# RP_ComputeModule3_rev_3_0_GPIOs.net
KiCad netlist of a schematic drawn in Altium Designer
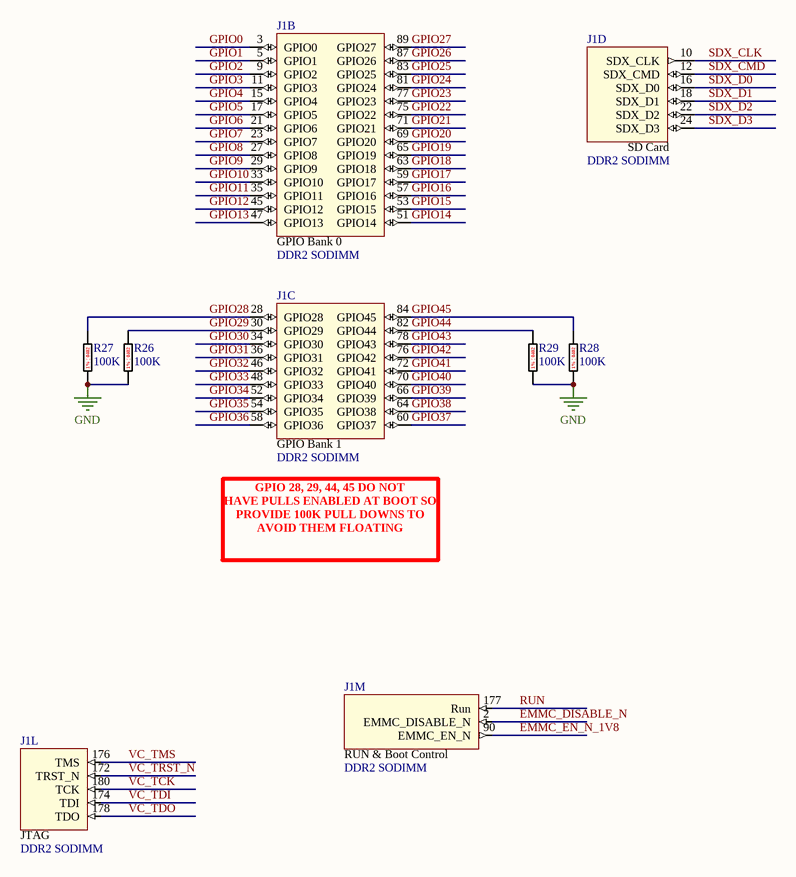
[diagram p0: RP_ComputeModule3_rev.3.0_GPIOs.SchDoc]

(export (version "E")
  (design (tool "Eeschema 10.0.6"))
  (components
    (comp (ref "J1")
      (value "DDR2 SODIMM")
      (footprint "TE 1473005-4 (DDR2 SO-DIMM)")
      (description "TE CONNECTIVITY / AMP         1473005-4             SOCKET IC, DIMM, DDR2, 1.8V, 200WAY")
      (fields
        (field (name "MANUFACTURER") "TE Connectivity")
        (field (name "MANUFACTURER PART NUMBER") "1473005-4")
      )
      (libsource (lib "TEConnectivity_AMP") (part "1473005-4"))
    )
    (comp (ref "R26")
      (value "100K")
      (footprint "RES0402")
      (description "Thick Film Resistors - SMD 0.125W 100Kohm 1% 200ppm")
      (fields
        (field (name "MANUFACTURER") "KOA Speer")
        (field (name "MANUFACTURER PART NUMBER") "SG73P1ETTP1003F")
      )
      (libsource (lib "KOA_Resistors") (part "SG73P1ETTP1003F"))
    )
    (comp (ref "R27")
      (value "100K")
      (footprint "RES0402")
      (description "Thick Film Resistors - SMD 0.125W 100Kohm 1% 200ppm")
      (fields
        (field (name "MANUFACTURER") "KOA Speer")
        (field (name "MANUFACTURER PART NUMBER") "SG73P1ETTP1003F")
      )
      (libsource (lib "KOA_Resistors") (part "SG73P1ETTP1003F"))
    )
    (comp (ref "R28")
      (value "100K")
      (footprint "RES0402")
      (description "Thick Film Resistors - SMD 0.125W 100Kohm 1% 200ppm")
      (fields
        (field (name "MANUFACTURER") "KOA Speer")
        (field (name "MANUFACTURER PART NUMBER") "SG73P1ETTP1003F")
      )
      (libsource (lib "KOA_Resistors") (part "SG73P1ETTP1003F"))
    )
    (comp (ref "R29")
      (value "100K")
      (footprint "RES0402")
      (description "Thick Film Resistors - SMD 0.125W 100Kohm 1% 200ppm")
      (fields
        (field (name "MANUFACTURER") "KOA Speer")
        (field (name "MANUFACTURER PART NUMBER") "SG73P1ETTP1003F")
      )
      (libsource (lib "KOA_Resistors") (part "SG73P1ETTP1003F"))
    )
  )
  (nets
    (net (code "1") (name "/EMMC_DISABLE_N") (class "Default")
      (node (ref "J1") (pin "2") (pinfunction "EMMC_DISABLE_N_2") (pintype "input"))
    )
    (net (code "2") (name "/EMMC_EN_N_1V8") (class "Default")
      (node (ref "J1") (pin "90") (pinfunction "EMMC_EN_N_90") (pintype "output"))
    )
    (net (code "3") (name "/GPIO0") (class "Default")
      (node (ref "J1") (pin "3") (pinfunction "GPIO0_3") (pintype "bidirectional"))
    )
    (net (code "4") (name "/GPIO1") (class "Default")
      (node (ref "J1") (pin "5") (pinfunction "GPIO1_5") (pintype "bidirectional"))
    )
    (net (code "5") (name "/GPIO2") (class "Default")
      (node (ref "J1") (pin "9") (pinfunction "GPIO2_9") (pintype "bidirectional"))
    )
    (net (code "6") (name "/GPIO3") (class "Default")
      (node (ref "J1") (pin "11") (pinfunction "GPIO3_11") (pintype "bidirectional"))
    )
    (net (code "7") (name "/GPIO4") (class "Default")
      (node (ref "J1") (pin "15") (pinfunction "GPIO4_15") (pintype "bidirectional"))
    )
    (net (code "8") (name "/GPIO5") (class "Default")
      (node (ref "J1") (pin "17") (pinfunction "GPIO5_17") (pintype "bidirectional"))
    )
    (net (code "9") (name "/GPIO6") (class "Default")
      (node (ref "J1") (pin "21") (pinfunction "GPIO6_21") (pintype "bidirectional"))
    )
    (net (code "10") (name "/GPIO7") (class "Default")
      (node (ref "J1") (pin "23") (pinfunction "GPIO7_23") (pintype "bidirectional"))
    )
    (net (code "11") (name "/GPIO8") (class "Default")
      (node (ref "J1") (pin "27") (pinfunction "GPIO8_27") (pintype "bidirectional"))
    )
    (net (code "12") (name "/GPIO9") (class "Default")
      (node (ref "J1") (pin "29") (pinfunction "GPIO9_29") (pintype "bidirectional"))
    )
    (net (code "13") (name "/GPIO10") (class "Default")
      (node (ref "J1") (pin "33") (pinfunction "GPIO10_33") (pintype "bidirectional"))
    )
    (net (code "14") (name "/GPIO11") (class "Default")
      (node (ref "J1") (pin "35") (pinfunction "GPIO11_35") (pintype "bidirectional"))
    )
    (net (code "15") (name "/GPIO12") (class "Default")
      (node (ref "J1") (pin "45") (pinfunction "GPIO12_45") (pintype "bidirectional"))
    )
    (net (code "16") (name "/GPIO13") (class "Default")
      (node (ref "J1") (pin "47") (pinfunction "GPIO13_47") (pintype "bidirectional"))
    )
    (net (code "17") (name "/GPIO14") (class "Default")
      (node (ref "J1") (pin "51") (pinfunction "GPIO14_51") (pintype "bidirectional"))
    )
    (net (code "18") (name "/GPIO15") (class "Default")
      (node (ref "J1") (pin "53") (pinfunction "GPIO15_53") (pintype "bidirectional"))
    )
    (net (code "19") (name "/GPIO16") (class "Default")
      (node (ref "J1") (pin "57") (pinfunction "GPIO16_57") (pintype "bidirectional"))
    )
    (net (code "20") (name "/GPIO17") (class "Default")
      (node (ref "J1") (pin "59") (pinfunction "GPIO17_59") (pintype "bidirectional"))
    )
    (net (code "21") (name "/GPIO18") (class "Default")
      (node (ref "J1") (pin "63") (pinfunction "GPIO18_63") (pintype "bidirectional"))
    )
    (net (code "22") (name "/GPIO19") (class "Default")
      (node (ref "J1") (pin "65") (pinfunction "GPIO19_65") (pintype "bidirectional"))
    )
    (net (code "23") (name "/GPIO20") (class "Default")
      (node (ref "J1") (pin "69") (pinfunction "GPIO20_69") (pintype "bidirectional"))
    )
    (net (code "24") (name "/GPIO21") (class "Default")
      (node (ref "J1") (pin "71") (pinfunction "GPIO21_71") (pintype "bidirectional"))
    )
    (net (code "25") (name "/GPIO22") (class "Default")
      (node (ref "J1") (pin "75") (pinfunction "GPIO22_75") (pintype "bidirectional"))
    )
    (net (code "26") (name "/GPIO23") (class "Default")
      (node (ref "J1") (pin "77") (pinfunction "GPIO23_77") (pintype "bidirectional"))
    )
    (net (code "27") (name "/GPIO24") (class "Default")
      (node (ref "J1") (pin "81") (pinfunction "GPIO24_81") (pintype "bidirectional"))
    )
    (net (code "28") (name "/GPIO25") (class "Default")
      (node (ref "J1") (pin "83") (pinfunction "GPIO25_83") (pintype "bidirectional"))
    )
    (net (code "29") (name "/GPIO26") (class "Default")
      (node (ref "J1") (pin "87") (pinfunction "GPIO26_87") (pintype "bidirectional"))
    )
    (net (code "30") (name "/GPIO27") (class "Default")
      (node (ref "J1") (pin "89") (pinfunction "GPIO27_89") (pintype "bidirectional"))
    )
    (net (code "31") (name "/GPIO28") (class "Default")
      (node (ref "J1") (pin "28") (pinfunction "GPIO28_28") (pintype "bidirectional"))
      (node (ref "R27") (pin "1") (pinfunction "1_1") (pintype "passive"))
    )
    (net (code "32") (name "/GPIO29") (class "Default")
      (node (ref "J1") (pin "30") (pinfunction "GPIO29_30") (pintype "bidirectional"))
      (node (ref "R26") (pin "1") (pinfunction "1_1") (pintype "passive"))
    )
    (net (code "33") (name "/GPIO30") (class "Default")
      (node (ref "J1") (pin "34") (pinfunction "GPIO30_34") (pintype "bidirectional"))
    )
    (net (code "34") (name "/GPIO31") (class "Default")
      (node (ref "J1") (pin "36") (pinfunction "GPIO31_36") (pintype "bidirectional"))
    )
    (net (code "35") (name "/GPIO32") (class "Default")
      (node (ref "J1") (pin "46") (pinfunction "GPIO32_46") (pintype "bidirectional"))
    )
    (net (code "36") (name "/GPIO33") (class "Default")
      (node (ref "J1") (pin "48") (pinfunction "GPIO33_48") (pintype "bidirectional"))
    )
    (net (code "37") (name "/GPIO34") (class "Default")
      (node (ref "J1") (pin "52") (pinfunction "GPIO34_52") (pintype "bidirectional"))
    )
    (net (code "38") (name "/GPIO35") (class "Default")
      (node (ref "J1") (pin "54") (pinfunction "GPIO35_54") (pintype "bidirectional"))
    )
    (net (code "39") (name "/GPIO36") (class "Default")
      (node (ref "J1") (pin "58") (pinfunction "GPIO36_58") (pintype "bidirectional"))
    )
    (net (code "40") (name "/GPIO37") (class "Default")
      (node (ref "J1") (pin "60") (pinfunction "GPIO37_60") (pintype "bidirectional"))
    )
    (net (code "41") (name "/GPIO38") (class "Default")
      (node (ref "J1") (pin "64") (pinfunction "GPIO38_64") (pintype "bidirectional"))
    )
    (net (code "42") (name "/GPIO39") (class "Default")
      (node (ref "J1") (pin "66") (pinfunction "GPIO39_66") (pintype "bidirectional"))
    )
    (net (code "43") (name "/GPIO40") (class "Default")
      (node (ref "J1") (pin "70") (pinfunction "GPIO40_70") (pintype "bidirectional"))
    )
    (net (code "44") (name "/GPIO41") (class "Default")
      (node (ref "J1") (pin "72") (pinfunction "GPIO41_72") (pintype "bidirectional"))
    )
    (net (code "45") (name "/GPIO42") (class "Default")
      (node (ref "J1") (pin "76") (pinfunction "GPIO42_76") (pintype "bidirectional"))
    )
    (net (code "46") (name "/GPIO43") (class "Default")
      (node (ref "J1") (pin "78") (pinfunction "GPIO43_78") (pintype "bidirectional"))
    )
    (net (code "47") (name "/GPIO44") (class "Default")
      (node (ref "J1") (pin "82") (pinfunction "GPIO44_82") (pintype "bidirectional"))
      (node (ref "R29") (pin "1") (pinfunction "1_1") (pintype "passive"))
    )
    (net (code "48") (name "/GPIO45") (class "Default")
      (node (ref "J1") (pin "84") (pinfunction "GPIO45_84") (pintype "bidirectional"))
      (node (ref "R28") (pin "1") (pinfunction "1_1") (pintype "passive"))
    )
    (net (code "49") (name "/RUN") (class "Default")
      (node (ref "J1") (pin "177") (pinfunction "Run_177") (pintype "input"))
    )
    (net (code "50") (name "/SDX_CLK") (class "Default")
      (node (ref "J1") (pin "10") (pinfunction "SDX_CLK_10") (pintype "output"))
    )
    (net (code "51") (name "/SDX_CMD") (class "Default")
      (node (ref "J1") (pin "12") (pinfunction "SDX_CMD_12") (pintype "bidirectional"))
    )
    (net (code "52") (name "/SDX_D0") (class "Default")
      (node (ref "J1") (pin "16") (pinfunction "SDX_D0_16") (pintype "bidirectional"))
    )
    (net (code "53") (name "/SDX_D1") (class "Default")
      (node (ref "J1") (pin "18") (pinfunction "SDX_D1_18") (pintype "bidirectional"))
    )
    (net (code "54") (name "/SDX_D2") (class "Default")
      (node (ref "J1") (pin "22") (pinfunction "SDX_D2_22") (pintype "bidirectional"))
    )
    (net (code "55") (name "/SDX_D3") (class "Default")
      (node (ref "J1") (pin "24") (pinfunction "SDX_D3_24") (pintype "bidirectional"))
    )
    (net (code "56") (name "/VC_TCK") (class "Default")
      (node (ref "J1") (pin "180") (pinfunction "TCK_180") (pintype "input"))
    )
    (net (code "57") (name "/VC_TDI") (class "Default")
      (node (ref "J1") (pin "174") (pinfunction "TDI_174") (pintype "input"))
    )
    (net (code "58") (name "/VC_TDO") (class "Default")
      (node (ref "J1") (pin "178") (pinfunction "TDO_178") (pintype "input"))
    )
    (net (code "59") (name "/VC_TMS") (class "Default")
      (node (ref "J1") (pin "176") (pinfunction "TMS_176") (pintype "input"))
    )
    (net (code "60") (name "/VC_TRST_N") (class "Default")
      (node (ref "J1") (pin "172") (pinfunction "TRST_N_172") (pintype "input"))
    )
    (net (code "61") (name "GND") (class "Default")
      (node (ref "R26") (pin "2") (pinfunction "2_2") (pintype "passive"))
      (node (ref "R27") (pin "2") (pinfunction "2_2") (pintype "passive"))
      (node (ref "R28") (pin "2") (pinfunction "2_2") (pintype "passive"))
      (node (ref "R29") (pin "2") (pinfunction "2_2") (pintype "passive"))
    )
  )
)
